# Templcd.net
KiCad netlist of a schematic drawn in EAGLE
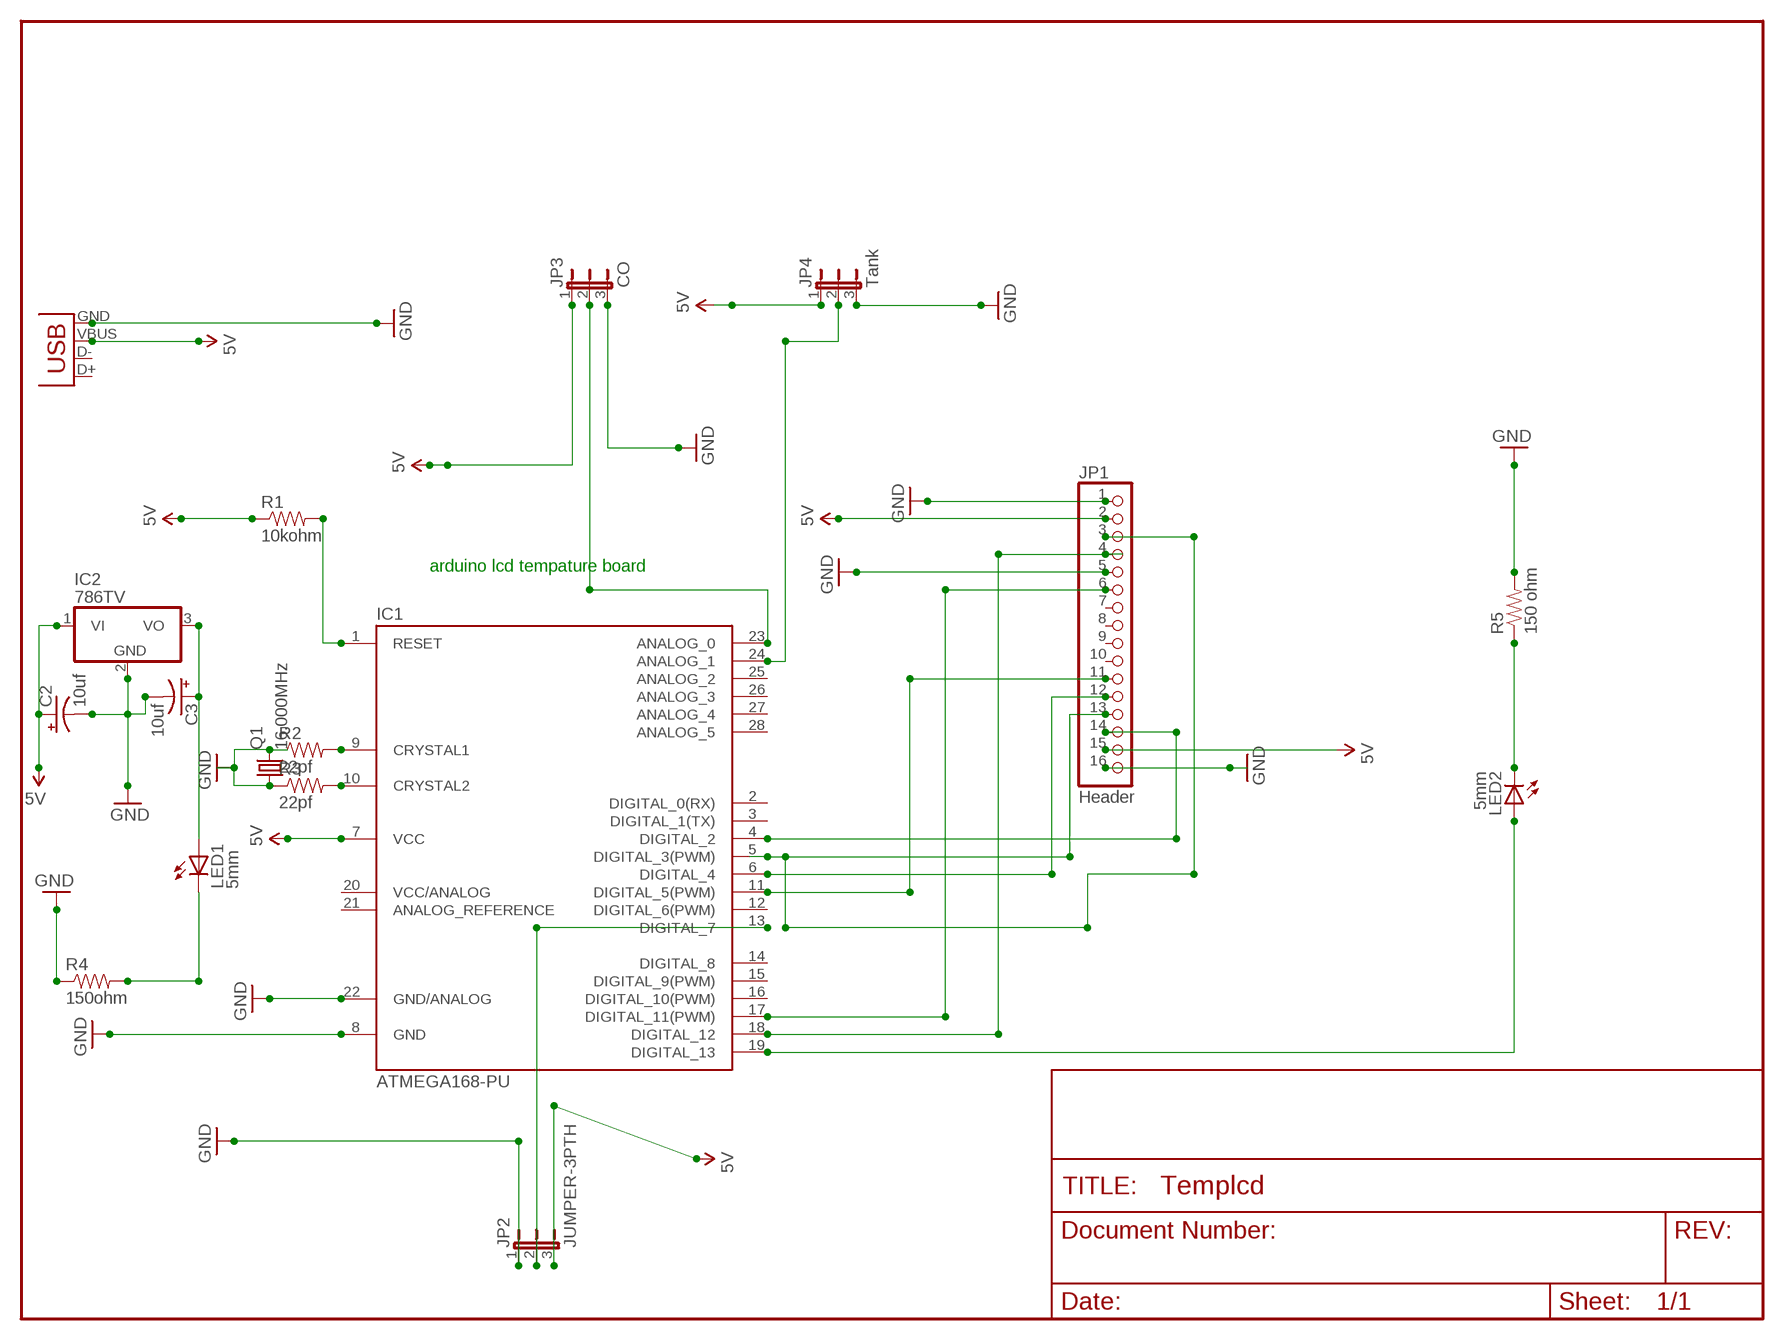
[diagram p0: schematic, sheet 1]

(export (version "E")
  (design (tool "Eeschema 10.0.6"))
  (components
    (comp (ref "C2")
      (value "10uf")
      (footprint "eagle-import:CPOL-RADIAL-100UF-25V")
      (libsource (lib "eagle-import") (part "CAP_POLPTH1"))
    )
    (comp (ref "C3")
      (value "10uf")
      (footprint "eagle-import:CPOL-RADIAL-100UF-25V")
      (libsource (lib "eagle-import") (part "CAP_POLPTH1"))
    )
    (comp (ref "IC1")
      (value "ATMEGA168-PU")
      (footprint "eagle-import:DIL28-3")
      (libsource (lib "eagle-import") (part "ATMEGA168-PU"))
    )
    (comp (ref "IC2")
      (value "786TV")
      (footprint "eagle-import:TO220V")
      (libsource (lib "eagle-import") (part "78TV6"))
    )
    (comp (ref "JP1")
      (value "Header")
      (footprint "eagle-import:1X16")
      (libsource (lib "eagle-import") (part "PINHD-1X16"))
    )
    (comp (ref "JP2")
      (value "JUMPER-3PTH")
      (footprint "eagle-import:1X03")
      (libsource (lib "eagle-import") (part "JUMPER-3PTH"))
    )
    (comp (ref "JP3")
      (value "CO")
      (footprint "eagle-import:JP2W")
      (libsource (lib "eagle-import") (part "JP2W"))
    )
    (comp (ref "JP4")
      (value "Tank")
      (footprint "eagle-import:JP2W")
      (libsource (lib "eagle-import") (part "JP2W"))
    )
    (comp (ref "LED1")
      (value "5mm")
      (footprint "eagle-import:LED5MM")
      (libsource (lib "eagle-import") (part "led_LED5MM"))
    )
    (comp (ref "LED2")
      (value "5mm")
      (footprint "eagle-import:LED5MM")
      (libsource (lib "eagle-import") (part "LED5MM"))
    )
    (comp (ref "Q1")
      (value "16.000MHz")
      (footprint "eagle-import:HC49U-V")
      (libsource (lib "eagle-import") (part "CRYSTALHC49U-V"))
    )
    (comp (ref "R1")
      (value "10kohm")
      (footprint "eagle-import:AXIAL-0.3")
      (libsource (lib "eagle-import") (part "RESISTORPTH1"))
    )
    (comp (ref "R2")
      (value "22pf")
      (footprint "eagle-import:AXIAL-0.3")
      (libsource (lib "eagle-import") (part "RESISTORPTH1"))
    )
    (comp (ref "R3")
      (value "22pf")
      (footprint "eagle-import:AXIAL-0.3")
      (libsource (lib "eagle-import") (part "RESISTORPTH1"))
    )
    (comp (ref "R4")
      (value "150ohm")
      (footprint "eagle-import:AXIAL-0.3")
      (libsource (lib "eagle-import") (part "RESISTORPTH1"))
    )
    (comp (ref "R5")
      (value "150 ohm")
      (footprint "eagle-import:AXIAL-0.3")
      (libsource (lib "eagle-import") (part "RESISTORPTH1"))
    )
    (comp (ref "X1")
      (value "USBPTH")
      (footprint "eagle-import:USB-B-PTH")
      (libsource (lib "eagle-import") (part "USBPTH"))
    )
  )
  (nets
    (net (code "1") (name "5V") (class "Default")
      (node (ref "C2") (pin "1") (pinfunction "+_1") (pintype "passive"))
      (node (ref "IC1") (pin "7") (pinfunction "VCC_7") (pintype "power_in"))
      (node (ref "IC2") (pin "1") (pinfunction "VI_1") (pintype "input"))
      (node (ref "JP1") (pin "15") (pinfunction "15_15") (pintype "passive"))
      (node (ref "JP1") (pin "2") (pinfunction "2_2") (pintype "passive"))
      (node (ref "JP2") (pin "3") (pinfunction "3_3") (pintype "passive"))
      (node (ref "JP3") (pin "1") (pinfunction "1_1") (pintype "passive"))
      (node (ref "JP4") (pin "1") (pinfunction "1_1") (pintype "passive"))
      (node (ref "R1") (pin "P$1") (pinfunction "1_P$1") (pintype "passive"))
      (node (ref "X1") (pin "VBUS") (pinfunction "VBUS_VBUS") (pintype "bidirectional"))
    )
    (net (code "2") (name "GND") (class "Default")
      (node (ref "C2") (pin "2") (pinfunction "-_2") (pintype "passive"))
      (node (ref "C3") (pin "2") (pinfunction "-_2") (pintype "passive"))
      (node (ref "IC1") (pin "22") (pinfunction "GND/ANALOG_22") (pintype "power_in"))
      (node (ref "IC1") (pin "8") (pinfunction "GND_8") (pintype "power_in"))
      (node (ref "IC2") (pin "2") (pinfunction "GND_2") (pintype "passive"))
      (node (ref "JP1") (pin "1") (pinfunction "1_1") (pintype "passive"))
      (node (ref "JP1") (pin "16") (pinfunction "16_16") (pintype "passive"))
      (node (ref "JP1") (pin "5") (pinfunction "5_5") (pintype "passive"))
      (node (ref "JP2") (pin "1") (pinfunction "1_1") (pintype "passive"))
      (node (ref "JP3") (pin "3") (pinfunction "3_3") (pintype "passive"))
      (node (ref "JP4") (pin "3") (pinfunction "3_3") (pintype "passive"))
      (node (ref "Q1") (pin "1") (pinfunction "1_1") (pintype "passive"))
      (node (ref "Q1") (pin "2") (pinfunction "2_2") (pintype "passive"))
      (node (ref "R2") (pin "P$1") (pinfunction "1_P$1") (pintype "passive"))
      (node (ref "R3") (pin "P$1") (pinfunction "1_P$1") (pintype "passive"))
      (node (ref "R4") (pin "P$1") (pinfunction "1_P$1") (pintype "passive"))
      (node (ref "R5") (pin "P$2") (pinfunction "2_P$2") (pintype "passive"))
      (node (ref "X1") (pin "GND") (pinfunction "GND_GND") (pintype "bidirectional"))
    )
    (net (code "3") (name "Net-(C3-+)") (class "Default")
      (node (ref "C3") (pin "1") (pinfunction "+_1") (pintype "passive"))
      (node (ref "IC2") (pin "3") (pinfunction "VO_3") (pintype "passive"))
      (node (ref "LED1") (pin "A") (pinfunction "A_A") (pintype "passive"))
    )
    (net (code "4") (name "Net-(IC1-ANALOG_0)") (class "Default")
      (node (ref "IC1") (pin "23") (pinfunction "ANALOG_0_23") (pintype "bidirectional"))
      (node (ref "JP3") (pin "2") (pinfunction "2_2") (pintype "passive"))
    )
    (net (code "5") (name "Net-(IC1-ANALOG_1)") (class "Default")
      (node (ref "IC1") (pin "24") (pinfunction "ANALOG_1_24") (pintype "bidirectional"))
      (node (ref "JP4") (pin "2") (pinfunction "2_2") (pintype "passive"))
    )
    (net (code "6") (name "Net-(IC1-CRYSTAL1)") (class "Default")
      (node (ref "IC1") (pin "9") (pinfunction "CRYSTAL1_9") (pintype "bidirectional"))
      (node (ref "R2") (pin "P$2") (pinfunction "2_P$2") (pintype "passive"))
    )
    (net (code "7") (name "Net-(IC1-CRYSTAL2)") (class "Default")
      (node (ref "IC1") (pin "10") (pinfunction "CRYSTAL2_10") (pintype "bidirectional"))
      (node (ref "R3") (pin "P$2") (pinfunction "2_P$2") (pintype "passive"))
    )
    (net (code "8") (name "Net-(IC1-DIGITAL_2)") (class "Default")
      (node (ref "IC1") (pin "4") (pinfunction "DIGITAL_2_4") (pintype "bidirectional"))
      (node (ref "JP1") (pin "14") (pinfunction "14_14") (pintype "passive"))
    )
    (net (code "9") (name "Net-(IC1-DIGITAL_3(PWM))") (class "Default")
      (node (ref "IC1") (pin "5") (pinfunction "DIGITAL_3(PWM)_5") (pintype "bidirectional"))
      (node (ref "JP1") (pin "13") (pinfunction "13_13") (pintype "passive"))
      (node (ref "JP1") (pin "3") (pinfunction "3_3") (pintype "passive"))
    )
    (net (code "10") (name "Net-(IC1-DIGITAL_4)") (class "Default")
      (node (ref "IC1") (pin "6") (pinfunction "DIGITAL_4_6") (pintype "bidirectional"))
      (node (ref "JP1") (pin "12") (pinfunction "12_12") (pintype "passive"))
    )
    (net (code "11") (name "Net-(IC1-DIGITAL_5(PWM))") (class "Default")
      (node (ref "IC1") (pin "11") (pinfunction "DIGITAL_5(PWM)_11") (pintype "bidirectional"))
      (node (ref "JP1") (pin "11") (pinfunction "11_11") (pintype "passive"))
    )
    (net (code "12") (name "Net-(IC1-DIGITAL_7)") (class "Default")
      (node (ref "IC1") (pin "13") (pinfunction "DIGITAL_7_13") (pintype "bidirectional"))
      (node (ref "JP2") (pin "2") (pinfunction "2_2") (pintype "passive"))
    )
    (net (code "13") (name "Net-(IC1-DIGITAL_11(PWM))") (class "Default")
      (node (ref "IC1") (pin "17") (pinfunction "DIGITAL_11(PWM)_17") (pintype "bidirectional"))
      (node (ref "JP1") (pin "6") (pinfunction "6_6") (pintype "passive"))
    )
    (net (code "14") (name "Net-(IC1-DIGITAL_12)") (class "Default")
      (node (ref "IC1") (pin "18") (pinfunction "DIGITAL_12_18") (pintype "bidirectional"))
      (node (ref "JP1") (pin "4") (pinfunction "4_4") (pintype "passive"))
    )
    (net (code "15") (name "Net-(IC1-DIGITAL_13)") (class "Default")
      (node (ref "IC1") (pin "19") (pinfunction "DIGITAL_13_19") (pintype "bidirectional"))
      (node (ref "LED2") (pin "A") (pinfunction "A_A") (pintype "passive"))
    )
    (net (code "16") (name "Net-(IC1-RESET)") (class "Default")
      (node (ref "IC1") (pin "1") (pinfunction "RESET_1") (pintype "bidirectional"))
      (node (ref "R1") (pin "P$2") (pinfunction "2_P$2") (pintype "passive"))
    )
    (net (code "17") (name "Net-(LED1-C)") (class "Default")
      (node (ref "LED1") (pin "K") (pinfunction "C_K") (pintype "passive"))
      (node (ref "R4") (pin "P$2") (pinfunction "2_P$2") (pintype "passive"))
    )
    (net (code "18") (name "Net-(LED2-C)") (class "Default")
      (node (ref "LED2") (pin "K") (pinfunction "C_K") (pintype "passive"))
      (node (ref "R5") (pin "P$1") (pinfunction "1_P$1") (pintype "passive"))
    )
    (net (code "19") (name "unconnected-(IC1-ANALOG_2-Pad25)") (class "Default")
      (node (ref "IC1") (pin "25") (pinfunction "ANALOG_2_25") (pintype "bidirectional"))
    )
    (net (code "20") (name "unconnected-(IC1-ANALOG_3-Pad26)") (class "Default")
      (node (ref "IC1") (pin "26") (pinfunction "ANALOG_3_26") (pintype "bidirectional"))
    )
    (net (code "21") (name "unconnected-(IC1-ANALOG_4-Pad27)") (class "Default")
      (node (ref "IC1") (pin "27") (pinfunction "ANALOG_4_27") (pintype "bidirectional"))
    )
    (net (code "22") (name "unconnected-(IC1-ANALOG_5-Pad28)") (class "Default")
      (node (ref "IC1") (pin "28") (pinfunction "ANALOG_5_28") (pintype "bidirectional"))
    )
    (net (code "23") (name "unconnected-(IC1-ANALOG_REFERENCE-Pad21)") (class "Default")
      (node (ref "IC1") (pin "21") (pinfunction "ANALOG_REFERENCE_21") (pintype "passive"))
    )
    (net (code "24") (name "unconnected-(IC1-DIGITAL_0(RX)-Pad2)") (class "Default")
      (node (ref "IC1") (pin "2") (pinfunction "DIGITAL_0(RX)_2") (pintype "bidirectional"))
    )
    (net (code "25") (name "unconnected-(IC1-DIGITAL_1(TX)-Pad3)") (class "Default")
      (node (ref "IC1") (pin "3") (pinfunction "DIGITAL_1(TX)_3") (pintype "bidirectional"))
    )
    (net (code "26") (name "unconnected-(IC1-DIGITAL_6(PWM)-Pad12)") (class "Default")
      (node (ref "IC1") (pin "12") (pinfunction "DIGITAL_6(PWM)_12") (pintype "bidirectional"))
    )
    (net (code "27") (name "unconnected-(IC1-DIGITAL_8-Pad14)") (class "Default")
      (node (ref "IC1") (pin "14") (pinfunction "DIGITAL_8_14") (pintype "bidirectional"))
    )
    (net (code "28") (name "unconnected-(IC1-DIGITAL_9(PWM)-Pad15)") (class "Default")
      (node (ref "IC1") (pin "15") (pinfunction "DIGITAL_9(PWM)_15") (pintype "bidirectional"))
    )
    (net (code "29") (name "unconnected-(IC1-DIGITAL_10(PWM)-Pad16)") (class "Default")
      (node (ref "IC1") (pin "16") (pinfunction "DIGITAL_10(PWM)_16") (pintype "bidirectional"))
    )
    (net (code "30") (name "unconnected-(IC1-VCC{slash}ANALOG-Pad20)") (class "Default")
      (node (ref "IC1") (pin "20") (pinfunction "VCC/ANALOG_20") (pintype "passive"))
    )
    (net (code "31") (name "unconnected-(JP1-Pad7)") (class "Default")
      (node (ref "JP1") (pin "7") (pinfunction "7_7") (pintype "passive"))
    )
    (net (code "32") (name "unconnected-(JP1-Pad8)") (class "Default")
      (node (ref "JP1") (pin "8") (pinfunction "8_8") (pintype "passive"))
    )
    (net (code "33") (name "unconnected-(JP1-Pad9)") (class "Default")
      (node (ref "JP1") (pin "9") (pinfunction "9_9") (pintype "passive"))
    )
    (net (code "34") (name "unconnected-(JP1-Pad10)") (class "Default")
      (node (ref "JP1") (pin "10") (pinfunction "10_10") (pintype "passive"))
    )
    (net (code "35") (name "unconnected-(X1-PadD+)") (class "Default")
      (node (ref "X1") (pin "D+") (pinfunction "D+_D+") (pintype "bidirectional"))
    )
    (net (code "36") (name "unconnected-(X1-PadD-)") (class "Default")
      (node (ref "X1") (pin "D-") (pinfunction "D-_D-") (pintype "bidirectional"))
    )
  )
)
